# Rad-detector.net
KiCad netlist of a schematic drawn in EAGLE
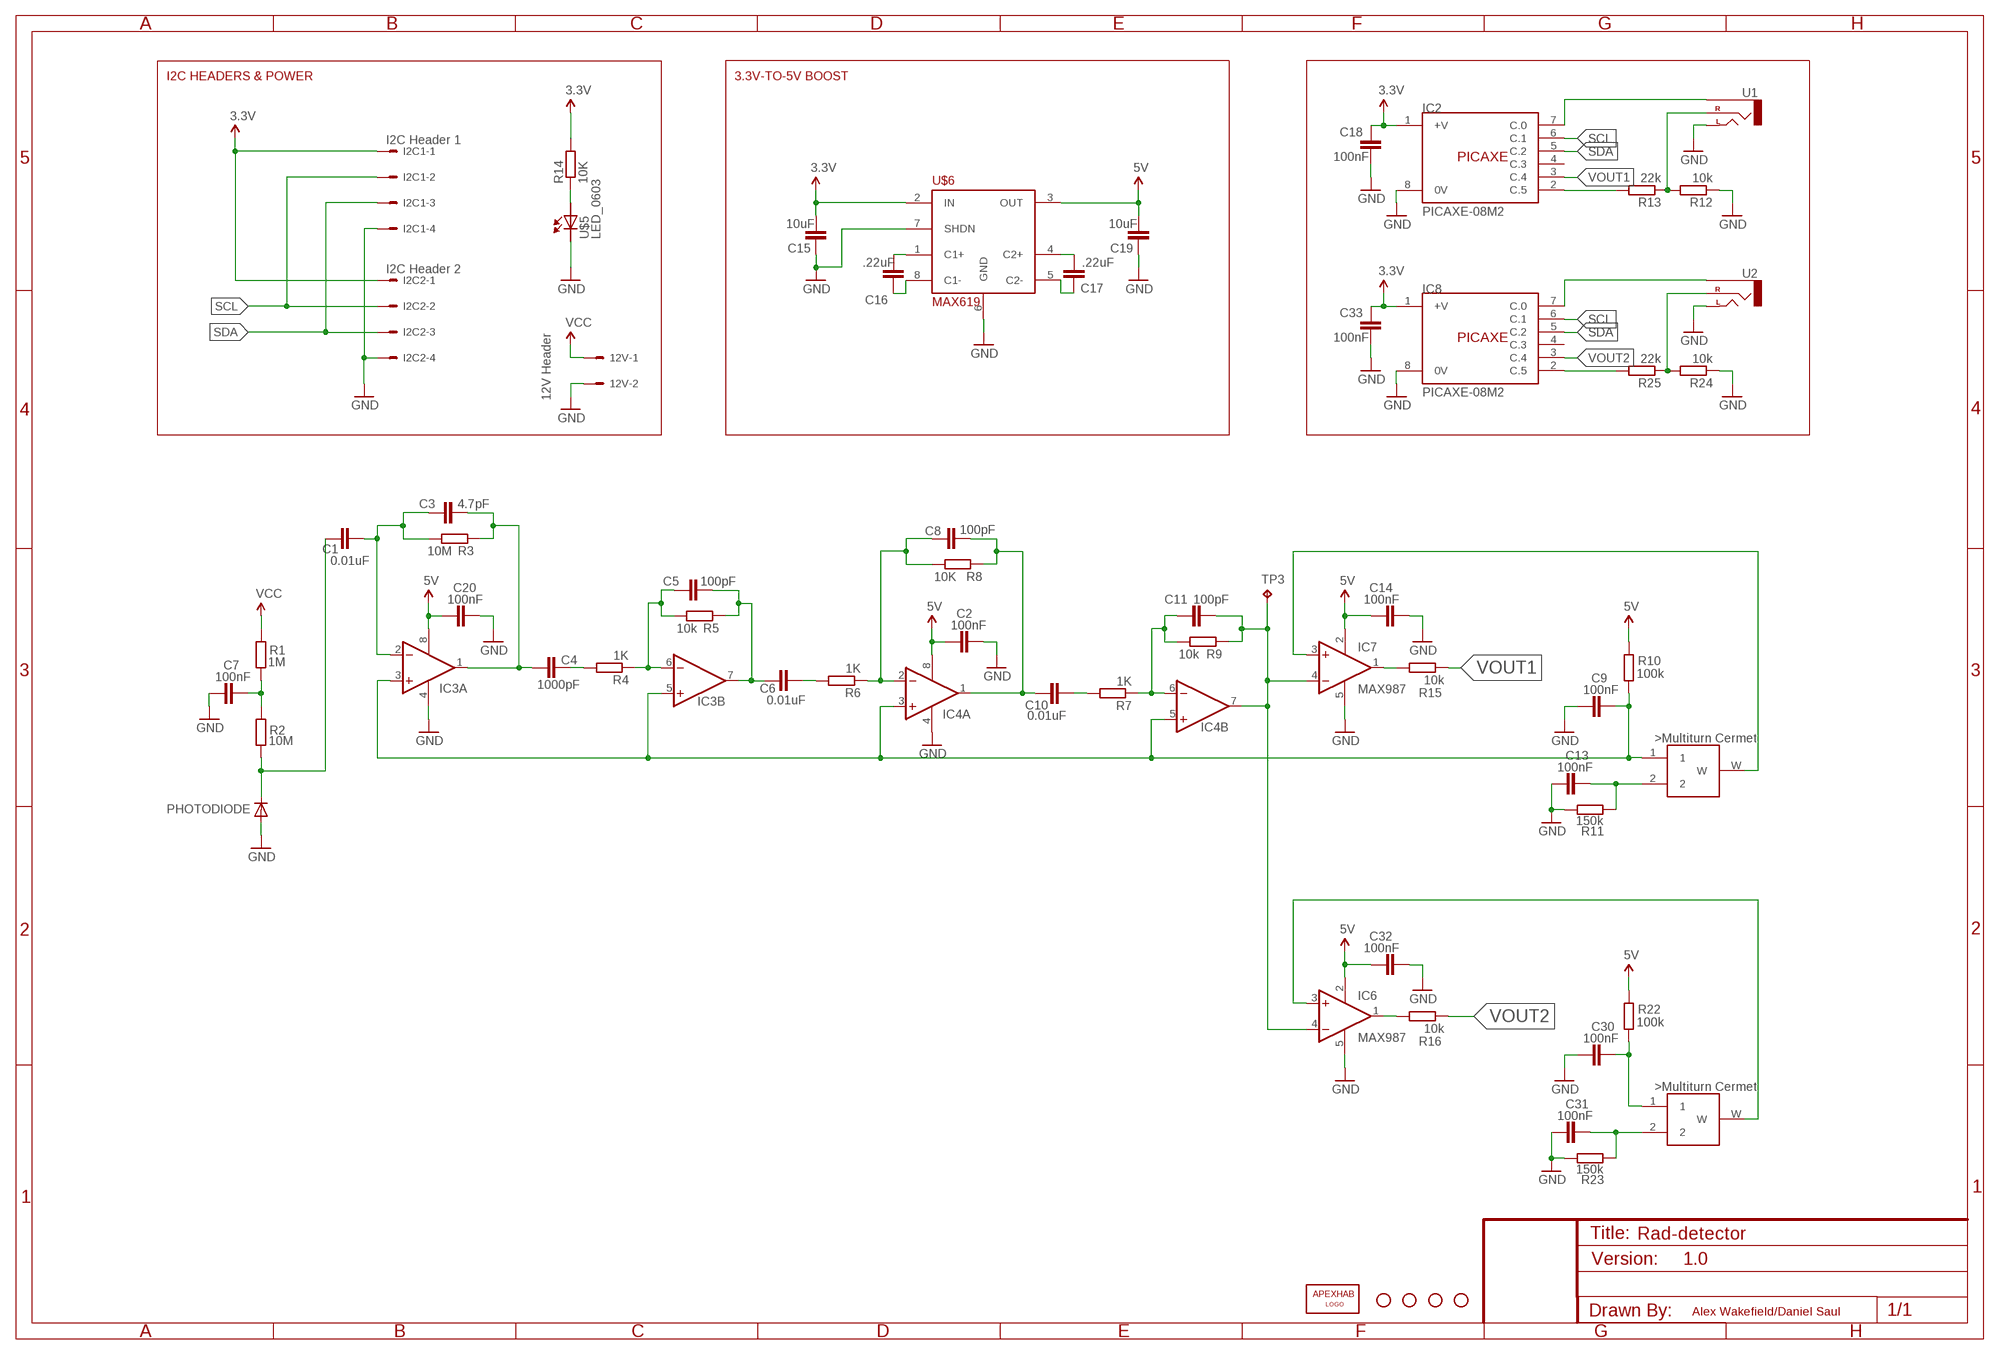
[diagram p0: schematic, sheet 1, part 1 of 2]
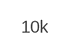
[diagram p1: schematic, sheet 1, part 2 of 2]

(export (version "E")
  (design (tool "Eeschema 10.0.6"))
  (components
    (comp (ref "12V")
      (value "12V Header")
      (footprint "eagle-import:6410-02")
      (libsource (lib "eagle-import") (part "22-?-0227-2021"))
    )
    (comp (ref "C1")
      (value "0.01uF")
      (footprint "eagle-import:C0805")
      (libsource (lib "eagle-import") (part "C-EUC0805"))
    )
    (comp (ref "C2")
      (value "100nF")
      (footprint "eagle-import:C0805")
      (libsource (lib "eagle-import") (part "C-EUC0805"))
    )
    (comp (ref "C3")
      (value "4.7pF")
      (footprint "eagle-import:C0805")
      (libsource (lib "eagle-import") (part "C-EUC0805"))
    )
    (comp (ref "C4")
      (value "1000pF")
      (footprint "eagle-import:C0805")
      (libsource (lib "eagle-import") (part "C-EUC0805"))
    )
    (comp (ref "C5")
      (value "100pF")
      (footprint "eagle-import:C0805")
      (libsource (lib "eagle-import") (part "C-EUC0805"))
    )
    (comp (ref "C6")
      (value "0.01uF")
      (footprint "eagle-import:C0805")
      (libsource (lib "eagle-import") (part "C-EUC0805"))
    )
    (comp (ref "C7")
      (value "100nF")
      (footprint "eagle-import:C0805")
      (libsource (lib "eagle-import") (part "C-EUC0805"))
    )
    (comp (ref "C8")
      (value "100pF")
      (footprint "eagle-import:C0805")
      (libsource (lib "eagle-import") (part "C-EUC0805"))
    )
    (comp (ref "C9")
      (value "100nF")
      (footprint "eagle-import:C0805")
      (libsource (lib "eagle-import") (part "C-EUC0805"))
    )
    (comp (ref "C10")
      (value "0.01uF")
      (footprint "eagle-import:C0805")
      (libsource (lib "eagle-import") (part "C-EUC0805"))
    )
    (comp (ref "C11")
      (value "100pF")
      (footprint "eagle-import:C0805")
      (libsource (lib "eagle-import") (part "C-EUC0805"))
    )
    (comp (ref "C13")
      (value "100nF")
      (footprint "eagle-import:C0805")
      (libsource (lib "eagle-import") (part "C-EUC0805"))
    )
    (comp (ref "C14")
      (value "100nF")
      (footprint "eagle-import:C0805")
      (libsource (lib "eagle-import") (part "C-EUC0805"))
    )
    (comp (ref "C15")
      (value "10uF")
      (footprint "eagle-import:C0805")
      (libsource (lib "eagle-import") (part "C-EUC0805"))
    )
    (comp (ref "C16")
      (value ".22uF")
      (footprint "eagle-import:C0805")
      (libsource (lib "eagle-import") (part "C-EUC0805"))
    )
    (comp (ref "C17")
      (value ".22uF")
      (footprint "eagle-import:C0805")
      (libsource (lib "eagle-import") (part "C-EUC0805"))
    )
    (comp (ref "C18")
      (value "100nF")
      (footprint "eagle-import:C0805")
      (libsource (lib "eagle-import") (part "C-EUC0805"))
    )
    (comp (ref "C19")
      (value "10uF")
      (footprint "eagle-import:C0805")
      (libsource (lib "eagle-import") (part "C-EUC0805"))
    )
    (comp (ref "C20")
      (value "100nF")
      (footprint "eagle-import:C0805")
      (libsource (lib "eagle-import") (part "C-EUC0805"))
    )
    (comp (ref "C30")
      (value "100nF")
      (footprint "eagle-import:C0805")
      (libsource (lib "eagle-import") (part "C-EUC0805"))
    )
    (comp (ref "C31")
      (value "100nF")
      (footprint "eagle-import:C0805")
      (libsource (lib "eagle-import") (part "C-EUC0805"))
    )
    (comp (ref "C32")
      (value "100nF")
      (footprint "eagle-import:C0805")
      (libsource (lib "eagle-import") (part "C-EUC0805"))
    )
    (comp (ref "C33")
      (value "100nF")
      (footprint "eagle-import:C0805")
      (libsource (lib "eagle-import") (part "C-EUC0805"))
    )
    (comp (ref "I2C1")
      (value "I2C Header 1")
      (footprint "eagle-import:6410-04")
      (libsource (lib "eagle-import") (part "22-?-0427-2041"))
    )
    (comp (ref "I2C2")
      (value "I2C Header 2")
      (footprint "eagle-import:6410-04")
      (libsource (lib "eagle-import") (part "22-?-0427-2041"))
    )
    (comp (ref "IC2")
      (value "PICAXE-08M2")
      (footprint "eagle-import:SOIC8")
      (libsource (lib "eagle-import") (part "PICAXE-08M2"))
    )
    (comp (ref "IC3")
      (value "max4477")
      (footprint "eagle-import:SO08")
      (libsource (lib "eagle-import") (part "CA3240ED"))
    )
    (comp (ref "IC4")
      (value "<AX4477")
      (footprint "eagle-import:SO08")
      (libsource (lib "eagle-import") (part "CA3240ED"))
    )
    (comp (ref "IC6")
      (value "MAX987")
      (footprint "eagle-import:SOT23-5")
      (libsource (lib "eagle-import") (part "MCP601R"))
    )
    (comp (ref "IC7")
      (value "MAX987")
      (footprint "eagle-import:SOT23-5")
      (libsource (lib "eagle-import") (part "MCP601R"))
    )
    (comp (ref "IC8")
      (value "PICAXE-08M2")
      (footprint "eagle-import:SOIC8")
      (libsource (lib "eagle-import") (part "PICAXE-08M2"))
    )
    (comp (ref "JP1")
      (value "APEXHAB-LOGO_APEX")
      (footprint "eagle-import:APEX-LOGO")
      (libsource (lib "eagle-import") (part "APEXHAB-LOGO_APEX"))
    )
    (comp (ref "JP2")
      (value "STAND-OFF")
      (footprint "eagle-import:STAND-OFF")
      (libsource (lib "eagle-import") (part "STAND-OFF"))
    )
    (comp (ref "JP3")
      (value "STAND-OFF")
      (footprint "eagle-import:STAND-OFF")
      (libsource (lib "eagle-import") (part "STAND-OFF"))
    )
    (comp (ref "JP4")
      (value "STAND-OFF")
      (footprint "eagle-import:STAND-OFF")
      (libsource (lib "eagle-import") (part "STAND-OFF"))
    )
    (comp (ref "JP5")
      (value "STAND-OFF")
      (footprint "eagle-import:STAND-OFF")
      (libsource (lib "eagle-import") (part "STAND-OFF"))
    )
    (comp (ref "PHOTODIODE")
      (value "DIODE-D-2.5")
      (footprint "eagle-import:D-2.5")
      (libsource (lib "eagle-import") (part "DIODE-D-2.5"))
    )
    (comp (ref "R1")
      (value "1M")
      (footprint "eagle-import:R0805")
      (libsource (lib "eagle-import") (part "R-EU_R0805"))
    )
    (comp (ref "R2")
      (value "10M")
      (footprint "eagle-import:R0805")
      (libsource (lib "eagle-import") (part "R-EU_R0805"))
    )
    (comp (ref "R3")
      (value "10M")
      (footprint "eagle-import:R0805")
      (libsource (lib "eagle-import") (part "R-EU_R0805"))
    )
    (comp (ref "R4")
      (value "1K")
      (footprint "eagle-import:R0805")
      (libsource (lib "eagle-import") (part "R-EU_R0805"))
    )
    (comp (ref "R5")
      (value "10k")
      (footprint "eagle-import:R0805")
      (libsource (lib "eagle-import") (part "R-EU_R0805"))
    )
    (comp (ref "R6")
      (value "1K")
      (footprint "eagle-import:R0805")
      (libsource (lib "eagle-import") (part "R-EU_R0805"))
    )
    (comp (ref "R7")
      (value "1K")
      (footprint "eagle-import:R0805")
      (libsource (lib "eagle-import") (part "R-EU_R0805"))
    )
    (comp (ref "R8")
      (value "10K")
      (footprint "eagle-import:R0805")
      (libsource (lib "eagle-import") (part "R-EU_R0805"))
    )
    (comp (ref "R9")
      (value "10k")
      (footprint "eagle-import:R0805")
      (libsource (lib "eagle-import") (part "R-EU_R0805"))
    )
    (comp (ref "R10")
      (value "100k")
      (footprint "eagle-import:R0805")
      (libsource (lib "eagle-import") (part "R-EU_R0805"))
    )
    (comp (ref "R11")
      (value "150k")
      (footprint "eagle-import:R0805")
      (libsource (lib "eagle-import") (part "R-EU_R0805"))
    )
    (comp (ref "R12")
      (value "10k")
      (footprint "eagle-import:R0805")
      (libsource (lib "eagle-import") (part "R-EU_R0805"))
    )
    (comp (ref "R13")
      (value "22k")
      (footprint "eagle-import:R0805")
      (libsource (lib "eagle-import") (part "R-EU_R0805"))
    )
    (comp (ref "R14")
      (value "10K")
      (footprint "eagle-import:R0805")
      (libsource (lib "eagle-import") (part "R-EU_R0805"))
    )
    (comp (ref "R15")
      (value "10k")
      (footprint "eagle-import:R0805")
      (libsource (lib "eagle-import") (part "R-EU_R0805"))
    )
    (comp (ref "R16")
      (value "10k")
      (footprint "eagle-import:R0805")
      (libsource (lib "eagle-import") (part "R-EU_R0805"))
    )
    (comp (ref "R22")
      (value "100k")
      (footprint "eagle-import:R0805")
      (libsource (lib "eagle-import") (part "R-EU_R0805"))
    )
    (comp (ref "R23")
      (value "150k")
      (footprint "eagle-import:R0805")
      (libsource (lib "eagle-import") (part "R-EU_R0805"))
    )
    (comp (ref "R24")
      (value "10k")
      (footprint "eagle-import:R0805")
      (libsource (lib "eagle-import") (part "R-EU_R0805"))
    )
    (comp (ref "R25")
      (value "22k")
      (footprint "eagle-import:R0805")
      (libsource (lib "eagle-import") (part "R-EU_R0805"))
    )
    (comp (ref "TP3")
      (value "TPTP10SQ")
      (footprint "eagle-import:TP10SQ")
      (libsource (lib "eagle-import") (part "TPTP10SQ"))
    )
    (comp (ref "U$3")
      (value "YL_SMT_11-TURN_CERMET_TRIMMER,_10K_0.25W")
      (footprint "eagle-import:YL_SMT_11-TURN_CERMET_TRIMMER,_10K_0.25W")
      (libsource (lib "eagle-import") (part "YL_SMT_11-TURN_CERMET_TRIMMER,_10K_0.25W"))
    )
    (comp (ref "U$4")
      (value "YL_SMT_11-TURN_CERMET_TRIMMER,_10K_0.25W")
      (footprint "eagle-import:YL_SMT_11-TURN_CERMET_TRIMMER,_10K_0.25W")
      (libsource (lib "eagle-import") (part "YL_SMT_11-TURN_CERMET_TRIMMER,_10K_0.25W"))
    )
    (comp (ref "U$5")
      (value "LED_0603")
      (footprint "eagle-import:CHIPLED_0603")
      (libsource (lib "eagle-import") (part "LED_0603"))
    )
    (comp (ref "U$6")
      (value "MAX619")
      (footprint "eagle-import:SO8")
      (libsource (lib "eagle-import") (part "MAX619"))
    )
    (comp (ref "U1")
      (value "AUDIO-JACKPTH")
      (footprint "eagle-import:AUDIO-JACK")
      (libsource (lib "eagle-import") (part "AUDIO-JACKPTH"))
    )
    (comp (ref "U2")
      (value "AUDIO-JACKPTH")
      (footprint "eagle-import:AUDIO-JACK")
      (libsource (lib "eagle-import") (part "AUDIO-JACKPTH"))
    )
  )
  (nets
    (net (code "1") (name "3.3V") (class "Default")
      (node (ref "C15") (pin "2") (pinfunction "2_2") (pintype "passive"))
      (node (ref "C18") (pin "1") (pinfunction "1_1") (pintype "passive"))
      (node (ref "C33") (pin "1") (pinfunction "1_1") (pintype "passive"))
      (node (ref "I2C1") (pin "1") (pinfunction "S_1") (pintype "passive"))
      (node (ref "I2C2") (pin "1") (pinfunction "S_1") (pintype "passive"))
      (node (ref "IC2") (pin "1") (pinfunction "+V_1") (pintype "power_in"))
      (node (ref "IC8") (pin "1") (pinfunction "+V_1") (pintype "power_in"))
      (node (ref "R14") (pin "2") (pinfunction "2_2") (pintype "passive"))
      (node (ref "U$6") (pin "2") (pinfunction "IN_2") (pintype "bidirectional"))
    )
    (net (code "2") (name "5V") (class "Default")
      (node (ref "C14") (pin "1") (pinfunction "1_1") (pintype "passive"))
      (node (ref "C19") (pin "2") (pinfunction "2_2") (pintype "passive"))
      (node (ref "C2") (pin "1") (pinfunction "1_1") (pintype "passive"))
      (node (ref "C20") (pin "1") (pinfunction "1_1") (pintype "passive"))
      (node (ref "C32") (pin "1") (pinfunction "1_1") (pintype "passive"))
      (node (ref "IC3") (pin "8") (pinfunction "V+_8") (pintype "power_in"))
      (node (ref "IC4") (pin "8") (pinfunction "V+_8") (pintype "power_in"))
      (node (ref "IC6") (pin "2") (pinfunction "V+_2") (pintype "power_in"))
      (node (ref "IC7") (pin "2") (pinfunction "V+_2") (pintype "power_in"))
      (node (ref "R10") (pin "1") (pinfunction "1_1") (pintype "passive"))
      (node (ref "R22") (pin "1") (pinfunction "1_1") (pintype "passive"))
      (node (ref "U$6") (pin "3") (pinfunction "OUT_3") (pintype "bidirectional"))
    )
    (net (code "3") (name "GND") (class "Default")
      (node (ref "12V") (pin "2") (pinfunction "S_2") (pintype "passive"))
      (node (ref "C13") (pin "1") (pinfunction "1_1") (pintype "passive"))
      (node (ref "C14") (pin "2") (pinfunction "2_2") (pintype "passive"))
      (node (ref "C15") (pin "1") (pinfunction "1_1") (pintype "passive"))
      (node (ref "C18") (pin "2") (pinfunction "2_2") (pintype "passive"))
      (node (ref "C19") (pin "1") (pinfunction "1_1") (pintype "passive"))
      (node (ref "C2") (pin "2") (pinfunction "2_2") (pintype "passive"))
      (node (ref "C20") (pin "2") (pinfunction "2_2") (pintype "passive"))
      (node (ref "C30") (pin "1") (pinfunction "1_1") (pintype "passive"))
      (node (ref "C31") (pin "1") (pinfunction "1_1") (pintype "passive"))
      (node (ref "C32") (pin "2") (pinfunction "2_2") (pintype "passive"))
      (node (ref "C33") (pin "2") (pinfunction "2_2") (pintype "passive"))
      (node (ref "C7") (pin "1") (pinfunction "1_1") (pintype "passive"))
      (node (ref "C9") (pin "1") (pinfunction "1_1") (pintype "passive"))
      (node (ref "I2C1") (pin "4") (pinfunction "S_4") (pintype "passive"))
      (node (ref "I2C2") (pin "4") (pinfunction "S_4") (pintype "passive"))
      (node (ref "IC2") (pin "8") (pinfunction "0V_8") (pintype "power_in"))
      (node (ref "IC3") (pin "4") (pinfunction "V-_4") (pintype "power_in"))
      (node (ref "IC4") (pin "4") (pinfunction "V-_4") (pintype "power_in"))
      (node (ref "IC6") (pin "5") (pinfunction "V-_5") (pintype "power_in"))
      (node (ref "IC7") (pin "5") (pinfunction "V-_5") (pintype "power_in"))
      (node (ref "IC8") (pin "8") (pinfunction "0V_8") (pintype "power_in"))
      (node (ref "PHOTODIODE") (pin "A") (pinfunction "A_A") (pintype "passive"))
      (node (ref "R11") (pin "2") (pinfunction "2_2") (pintype "passive"))
      (node (ref "R12") (pin "1") (pinfunction "1_1") (pintype "passive"))
      (node (ref "R23") (pin "2") (pinfunction "2_2") (pintype "passive"))
      (node (ref "R24") (pin "1") (pinfunction "1_1") (pintype "passive"))
      (node (ref "U$5") (pin "C") (pinfunction "C_C") (pintype "passive"))
      (node (ref "U$6") (pin "6") (pinfunction "GND_6") (pintype "bidirectional"))
      (node (ref "U$6") (pin "7") (pinfunction "SHDN_7") (pintype "bidirectional"))
      (node (ref "U1") (pin "TIP") (pinfunction "LEFT_TIP") (pintype "bidirectional"))
      (node (ref "U2") (pin "TIP") (pinfunction "LEFT_TIP") (pintype "bidirectional"))
    )
    (net (code "4") (name "Net-(C1-Pad1)") (class "Default")
      (node (ref "C1") (pin "1") (pinfunction "1_1") (pintype "passive"))
      (node (ref "PHOTODIODE") (pin "C") (pinfunction "C_C") (pintype "passive"))
      (node (ref "R2") (pin "1") (pinfunction "1_1") (pintype "passive"))
    )
    (net (code "5") (name "Net-(C4-Pad2)") (class "Default")
      (node (ref "C4") (pin "2") (pinfunction "2_2") (pintype "passive"))
      (node (ref "R4") (pin "2") (pinfunction "2_2") (pintype "passive"))
    )
    (net (code "6") (name "Net-(C6-Pad2)") (class "Default")
      (node (ref "C6") (pin "2") (pinfunction "2_2") (pintype "passive"))
      (node (ref "R6") (pin "2") (pinfunction "2_2") (pintype "passive"))
    )
    (net (code "7") (name "Net-(C7-Pad2)") (class "Default")
      (node (ref "C7") (pin "2") (pinfunction "2_2") (pintype "passive"))
      (node (ref "R1") (pin "1") (pinfunction "1_1") (pintype "passive"))
      (node (ref "R2") (pin "2") (pinfunction "2_2") (pintype "passive"))
    )
    (net (code "8") (name "Net-(C10-Pad2)") (class "Default")
      (node (ref "C10") (pin "2") (pinfunction "2_2") (pintype "passive"))
      (node (ref "R7") (pin "2") (pinfunction "2_2") (pintype "passive"))
    )
    (net (code "9") (name "Net-(C13-Pad2)") (class "Default")
      (node (ref "C13") (pin "2") (pinfunction "2_2") (pintype "passive"))
      (node (ref "R11") (pin "1") (pinfunction "1_1") (pintype "passive"))
      (node (ref "U$4") (pin "2") (pinfunction "2_2") (pintype "bidirectional"))
    )
    (net (code "10") (name "Net-(C30-Pad2)") (class "Default")
      (node (ref "C30") (pin "2") (pinfunction "2_2") (pintype "passive"))
      (node (ref "R22") (pin "2") (pinfunction "2_2") (pintype "passive"))
      (node (ref "U$3") (pin "1") (pinfunction "1_1") (pintype "bidirectional"))
    )
    (net (code "11") (name "Net-(C31-Pad2)") (class "Default")
      (node (ref "C31") (pin "2") (pinfunction "2_2") (pintype "passive"))
      (node (ref "R23") (pin "1") (pinfunction "1_1") (pintype "passive"))
      (node (ref "U$3") (pin "2") (pinfunction "2_2") (pintype "bidirectional"))
    )
    (net (code "12") (name "Net-(IC2-C.0)") (class "Default")
      (node (ref "IC2") (pin "7") (pinfunction "C.0_7") (pintype "bidirectional"))
      (node (ref "U1") (pin "SLEEVE") (pinfunction "SLEEVE_SLEEVE") (pintype "bidirectional"))
    )
    (net (code "13") (name "Net-(IC2-C.5)") (class "Default")
      (node (ref "IC2") (pin "2") (pinfunction "C.5_2") (pintype "bidirectional"))
      (node (ref "R13") (pin "2") (pinfunction "2_2") (pintype "passive"))
    )
    (net (code "14") (name "Net-(IC3A-+IN)") (class "Default")
      (node (ref "C9") (pin "2") (pinfunction "2_2") (pintype "passive"))
      (node (ref "IC3") (pin "3") (pinfunction "+IN_3") (pintype "input"))
      (node (ref "IC3") (pin "5") (pinfunction "+IN_5") (pintype "input"))
      (node (ref "IC4") (pin "3") (pinfunction "+IN_3") (pintype "input"))
      (node (ref "IC4") (pin "5") (pinfunction "+IN_5") (pintype "input"))
      (node (ref "R10") (pin "2") (pinfunction "2_2") (pintype "passive"))
      (node (ref "U$4") (pin "1") (pinfunction "1_1") (pintype "bidirectional"))
    )
    (net (code "15") (name "Net-(IC3A--IN)") (class "Default")
      (node (ref "C1") (pin "2") (pinfunction "2_2") (pintype "passive"))
      (node (ref "C3") (pin "1") (pinfunction "1_1") (pintype "passive"))
      (node (ref "IC3") (pin "2") (pinfunction "-IN_2") (pintype "input"))
      (node (ref "R3") (pin "2") (pinfunction "2_2") (pintype "passive"))
    )
    (net (code "16") (name "Net-(IC3A-OUT)") (class "Default")
      (node (ref "C3") (pin "2") (pinfunction "2_2") (pintype "passive"))
      (node (ref "C4") (pin "1") (pinfunction "1_1") (pintype "passive"))
      (node (ref "IC3") (pin "1") (pinfunction "OUT_1") (pintype "output"))
      (node (ref "R3") (pin "1") (pinfunction "1_1") (pintype "passive"))
    )
    (net (code "17") (name "Net-(IC3B--IN)") (class "Default")
      (node (ref "C5") (pin "1") (pinfunction "1_1") (pintype "passive"))
      (node (ref "IC3") (pin "6") (pinfunction "-IN_6") (pintype "input"))
      (node (ref "R4") (pin "1") (pinfunction "1_1") (pintype "passive"))
      (node (ref "R5") (pin "2") (pinfunction "2_2") (pintype "passive"))
    )
    (net (code "18") (name "Net-(IC3B-OUT)") (class "Default")
      (node (ref "C5") (pin "2") (pinfunction "2_2") (pintype "passive"))
      (node (ref "C6") (pin "1") (pinfunction "1_1") (pintype "passive"))
      (node (ref "IC3") (pin "7") (pinfunction "OUT_7") (pintype "output"))
      (node (ref "R5") (pin "1") (pinfunction "1_1") (pintype "passive"))
    )
    (net (code "19") (name "Net-(IC4A--IN)") (class "Default")
      (node (ref "C8") (pin "1") (pinfunction "1_1") (pintype "passive"))
      (node (ref "IC4") (pin "2") (pinfunction "-IN_2") (pintype "input"))
      (node (ref "R6") (pin "1") (pinfunction "1_1") (pintype "passive"))
      (node (ref "R8") (pin "2") (pinfunction "2_2") (pintype "passive"))
    )
    (net (code "20") (name "Net-(IC4A-OUT)") (class "Default")
      (node (ref "C10") (pin "1") (pinfunction "1_1") (pintype "passive"))
      (node (ref "C8") (pin "2") (pinfunction "2_2") (pintype "passive"))
      (node (ref "IC4") (pin "1") (pinfunction "OUT_1") (pintype "output"))
      (node (ref "R8") (pin "1") (pinfunction "1_1") (pintype "passive"))
    )
    (net (code "21") (name "Net-(IC4B--IN)") (class "Default")
      (node (ref "C11") (pin "1") (pinfunction "1_1") (pintype "passive"))
      (node (ref "IC4") (pin "6") (pinfunction "-IN_6") (pintype "input"))
      (node (ref "R7") (pin "1") (pinfunction "1_1") (pintype "passive"))
      (node (ref "R9") (pin "2") (pinfunction "2_2") (pintype "passive"))
    )
    (net (code "22") (name "Net-(IC4B-OUT)") (class "Default")
      (node (ref "C11") (pin "2") (pinfunction "2_2") (pintype "passive"))
      (node (ref "IC4") (pin "7") (pinfunction "OUT_7") (pintype "output"))
      (node (ref "IC6") (pin "4") (pinfunction "-IN_4") (pintype "input"))
      (node (ref "IC7") (pin "4") (pinfunction "-IN_4") (pintype "input"))
      (node (ref "R9") (pin "1") (pinfunction "1_1") (pintype "passive"))
      (node (ref "TP3") (pin "TP") (pinfunction "TP_TP") (pintype "input"))
    )
    (net (code "23") (name "Net-(IC6-+IN)") (class "Default")
      (node (ref "IC6") (pin "3") (pinfunction "+IN_3") (pintype "input"))
      (node (ref "U$3") (pin "W") (pinfunction "W_W") (pintype "bidirectional"))
    )
    (net (code "24") (name "Net-(IC6-OUT)") (class "Default")
      (node (ref "IC6") (pin "1") (pinfunction "OUT_1") (pintype "output"))
      (node (ref "R16") (pin "2") (pinfunction "2_2") (pintype "passive"))
    )
    (net (code "25") (name "Net-(IC7-+IN)") (class "Default")
      (node (ref "IC7") (pin "3") (pinfunction "+IN_3") (pintype "input"))
      (node (ref "U$4") (pin "W") (pinfunction "W_W") (pintype "bidirectional"))
    )
    (net (code "26") (name "Net-(IC7-OUT)") (class "Default")
      (node (ref "IC7") (pin "1") (pinfunction "OUT_1") (pintype "output"))
      (node (ref "R15") (pin "2") (pinfunction "2_2") (pintype "passive"))
    )
    (net (code "27") (name "Net-(IC8-C.0)") (class "Default")
      (node (ref "IC8") (pin "7") (pinfunction "C.0_7") (pintype "bidirectional"))
      (node (ref "U2") (pin "SLEEVE") (pinfunction "SLEEVE_SLEEVE") (pintype "bidirectional"))
    )
    (net (code "28") (name "Net-(IC8-C.5)") (class "Default")
      (node (ref "IC8") (pin "2") (pinfunction "C.5_2") (pintype "bidirectional"))
      (node (ref "R25") (pin "2") (pinfunction "2_2") (pintype "passive"))
    )
    (net (code "29") (name "Net-(R14-Pad1)") (class "Default")
      (node (ref "R14") (pin "1") (pinfunction "1_1") (pintype "passive"))
      (node (ref "U$5") (pin "A") (pinfunction "A_A") (pintype "passive"))
    )
    (net (code "30") (name "Net-(U$6-C1+)") (class "Default")
      (node (ref "C16") (pin "2") (pinfunction "2_2") (pintype "passive"))
      (node (ref "U$6") (pin "1") (pinfunction "C1+_1") (pintype "bidirectional"))
    )
    (net (code "31") (name "Net-(U$6-C1-)") (class "Default")
      (node (ref "C16") (pin "1") (pinfunction "1_1") (pintype "passive"))
      (node (ref "U$6") (pin "8") (pinfunction "C1-_8") (pintype "bidirectional"))
    )
    (net (code "32") (name "Net-(U$6-C2+)") (class "Default")
      (node (ref "C17") (pin "2") (pinfunction "2_2") (pintype "passive"))
      (node (ref "U$6") (pin "4") (pinfunction "C2+_4") (pintype "bidirectional"))
    )
    (net (code "33") (name "Net-(U$6-C2-)") (class "Default")
      (node (ref "C17") (pin "1") (pinfunction "1_1") (pintype "passive"))
      (node (ref "U$6") (pin "5") (pinfunction "C2-_5") (pintype "bidirectional"))
    )
    (net (code "34") (name "Net-(U1-RIGHT)") (class "Default")
      (node (ref "R12") (pin "2") (pinfunction "2_2") (pintype "passive"))
      (node (ref "R13") (pin "1") (pinfunction "1_1") (pintype "passive"))
      (node (ref "U1") (pin "RING") (pinfunction "RIGHT_RING") (pintype "bidirectional"))
    )
    (net (code "35") (name "Net-(U2-RIGHT)") (class "Default")
      (node (ref "R24") (pin "2") (pinfunction "2_2") (pintype "passive"))
      (node (ref "R25") (pin "1") (pinfunction "1_1") (pintype "passive"))
      (node (ref "U2") (pin "RING") (pinfunction "RIGHT_RING") (pintype "bidirectional"))
    )
    (net (code "36") (name "SCL") (class "Default")
      (node (ref "I2C1") (pin "2") (pinfunction "S_2") (pintype "passive"))
      (node (ref "I2C2") (pin "2") (pinfunction "S_2") (pintype "passive"))
      (node (ref "IC2") (pin "6") (pinfunction "C.1_6") (pintype "bidirectional"))
      (node (ref "IC8") (pin "6") (pinfunction "C.1_6") (pintype "bidirectional"))
    )
    (net (code "37") (name "SDA") (class "Default")
      (node (ref "I2C1") (pin "3") (pinfunction "S_3") (pintype "passive"))
      (node (ref "I2C2") (pin "3") (pinfunction "S_3") (pintype "passive"))
      (node (ref "IC2") (pin "5") (pinfunction "C.2_5") (pintype "bidirectional"))
      (node (ref "IC8") (pin "5") (pinfunction "C.2_5") (pintype "bidirectional"))
    )
    (net (code "38") (name "VCC") (class "Default")
      (node (ref "12V") (pin "1") (pinfunction "S_1") (pintype "passive"))
      (node (ref "R1") (pin "2") (pinfunction "2_2") (pintype "passive"))
    )
    (net (code "39") (name "VOUT1") (class "Default")
      (node (ref "IC2") (pin "3") (pinfunction "C.4_3") (pintype "bidirectional"))
      (node (ref "R15") (pin "1") (pinfunction "1_1") (pintype "passive"))
    )
    (net (code "40") (name "VOUT2") (class "Default")
      (node (ref "IC8") (pin "3") (pinfunction "C.4_3") (pintype "bidirectional"))
      (node (ref "R16") (pin "1") (pinfunction "1_1") (pintype "passive"))
    )
    (net (code "41") (name "unconnected-(IC2-C.3-Pad4)") (class "Default")
      (node (ref "IC2") (pin "4") (pinfunction "C.3_4") (pintype "bidirectional"))
    )
    (net (code "42") (name "unconnected-(IC8-C.3-Pad4)") (class "Default")
      (node (ref "IC8") (pin "4") (pinfunction "C.3_4") (pintype "bidirectional"))
    )
  )
)
